# Mega_Shield-v4.net
KiCad netlist of a schematic drawn in EAGLE
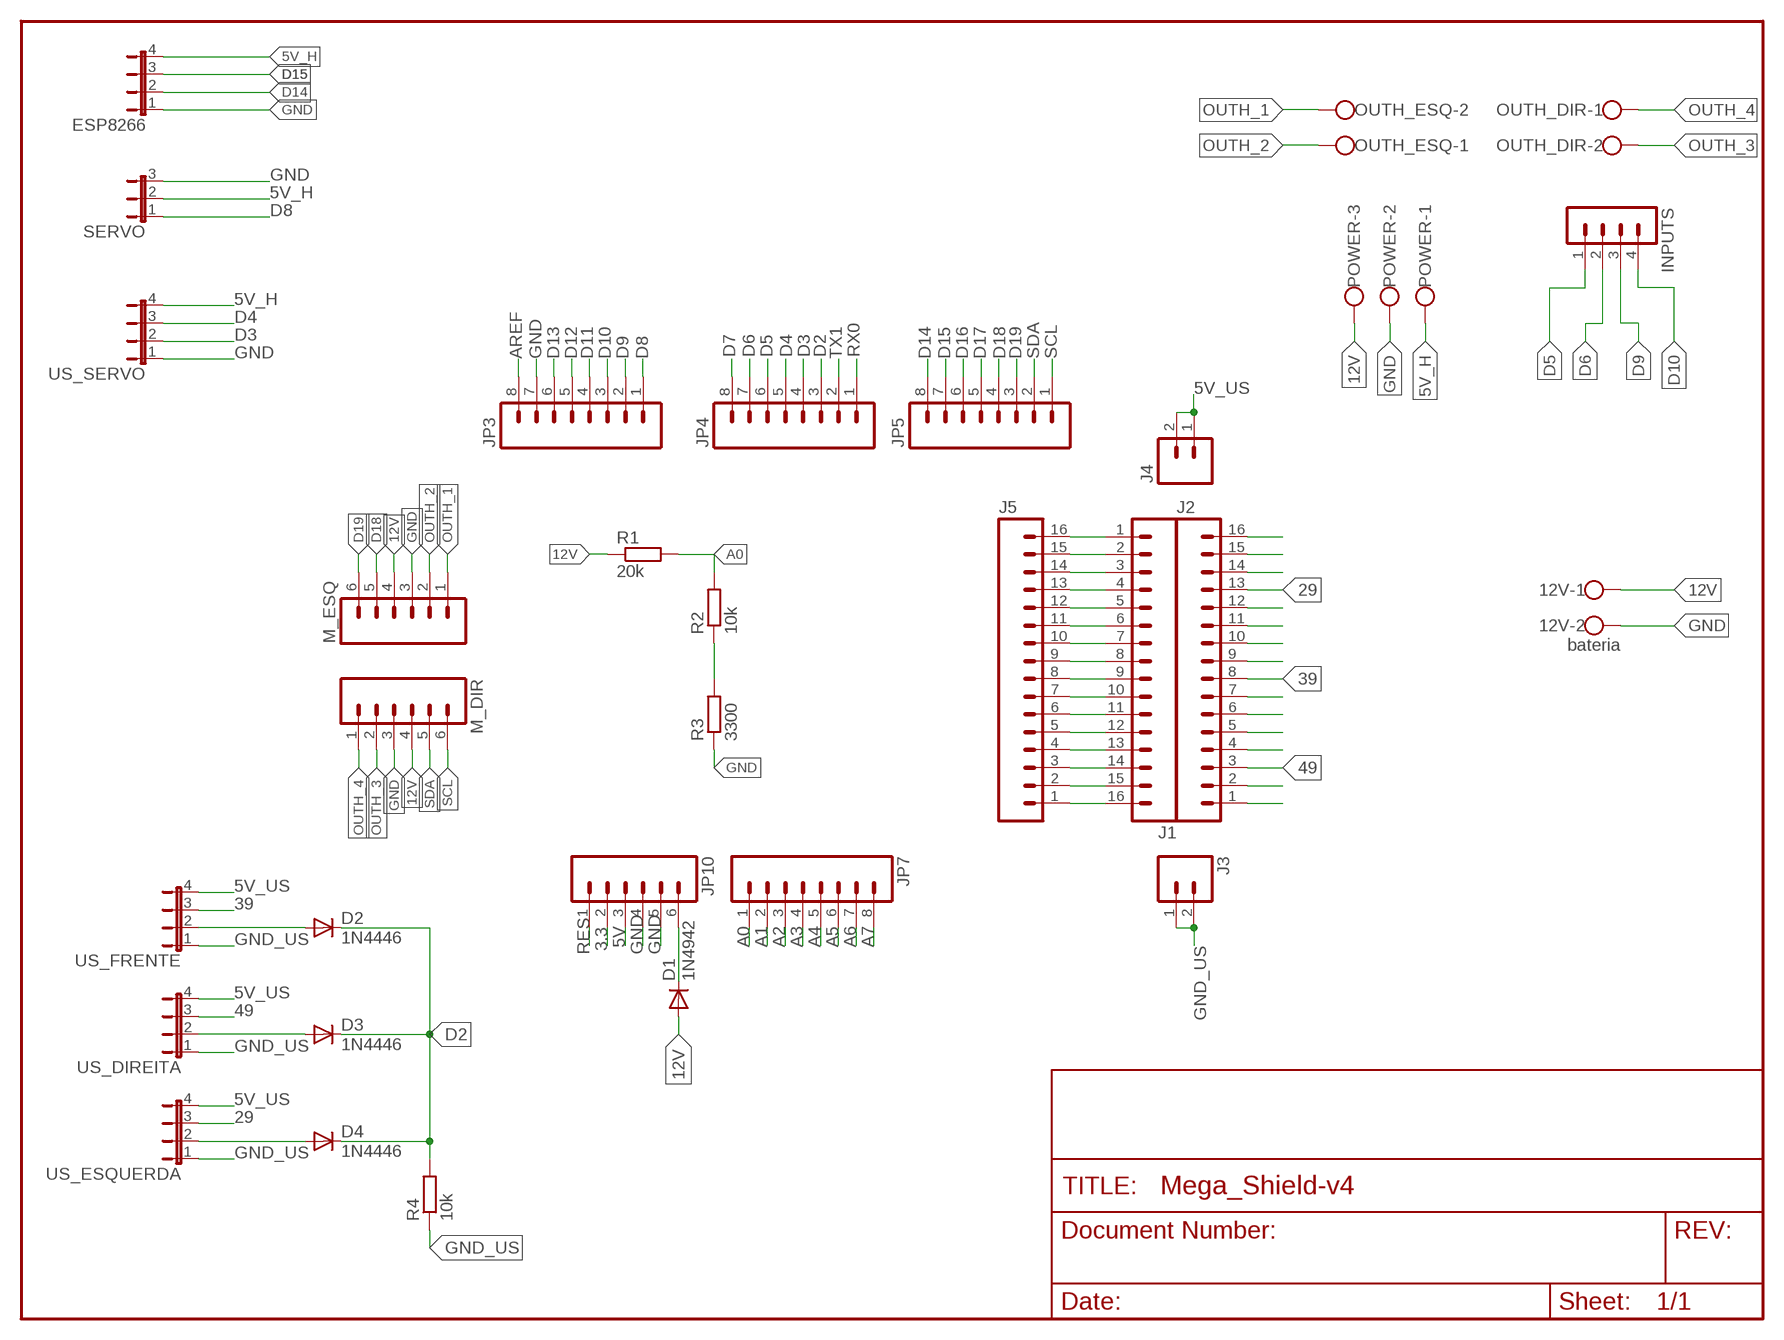
[diagram p0: schematic, sheet 1]

(export (version "E")
  (design (tool "Eeschema 10.0.6"))
  (components
    (comp (ref "12V")
      (value "bateria")
      (footprint "eagle-import:W237-102")
      (fields (field (name "MPN") "237-102"))
      (libsource (lib "eagle-import") (part "W237-102"))
    )
    (comp (ref "D1")
      (value "1N4942")
      (footprint "eagle-import:DO41-10")
      (libsource (lib "eagle-import") (part "1N4942"))
    )
    (comp (ref "D2")
      (value "1N4446")
      (footprint "eagle-import:DO35-10")
      (libsource (lib "eagle-import") (part "1N4446"))
    )
    (comp (ref "D3")
      (value "1N4446")
      (footprint "eagle-import:DO35-10")
      (libsource (lib "eagle-import") (part "1N4446"))
    )
    (comp (ref "D4")
      (value "1N4446")
      (footprint "eagle-import:DO35-10")
      (libsource (lib "eagle-import") (part "1N4446"))
    )
    (comp (ref "ESP8266")
      (value "JP4E")
      (footprint "eagle-import:JP4")
      (libsource (lib "eagle-import") (part "JP4E"))
    )
    (comp (ref "INPUTS")
      (value "MA04-1")
      (footprint "eagle-import:MA04-1")
      (libsource (lib "eagle-import") (part "MA04-1"))
    )
    (comp (ref "J1")
      (value "M16LOCK")
      (footprint "eagle-import:1X16_LOCK")
      (libsource (lib "eagle-import") (part "M16LOCK"))
    )
    (comp (ref "J2")
      (value "M16LOCK")
      (footprint "eagle-import:1X16_LOCK")
      (libsource (lib "eagle-import") (part "M16LOCK"))
    )
    (comp (ref "J3")
      (value "M02LOCK")
      (footprint "eagle-import:1X02_LOCK")
      (libsource (lib "eagle-import") (part "M02LOCK"))
    )
    (comp (ref "J4")
      (value "M02LOCK")
      (footprint "eagle-import:1X02_LOCK")
      (libsource (lib "eagle-import") (part "M02LOCK"))
    )
    (comp (ref "J5")
      (value "M16LOCK")
      (footprint "eagle-import:1X16_LOCK")
      (libsource (lib "eagle-import") (part "M16LOCK"))
    )
    (comp (ref "JP3")
      (value "M08LOCK")
      (footprint "eagle-import:1X08_LOCK")
      (libsource (lib "eagle-import") (part "M08LOCK"))
    )
    (comp (ref "JP4")
      (value "M08LOCK")
      (footprint "eagle-import:1X08_LOCK")
      (libsource (lib "eagle-import") (part "M08LOCK"))
    )
    (comp (ref "JP5")
      (value "M08LOCK")
      (footprint "eagle-import:1X08_LOCK")
      (libsource (lib "eagle-import") (part "M08LOCK"))
    )
    (comp (ref "JP7")
      (value "M08LOCK")
      (footprint "eagle-import:1X08_LOCK")
      (libsource (lib "eagle-import") (part "M08LOCK"))
    )
    (comp (ref "JP10")
      (value "M06LOCK")
      (footprint "eagle-import:1X06_LOCK")
      (libsource (lib "eagle-import") (part "M06LOCK"))
    )
    (comp (ref "M_DIR")
      (value "M06LOCK")
      (footprint "eagle-import:1X06_LOCK")
      (libsource (lib "eagle-import") (part "M06LOCK"))
    )
    (comp (ref "M_ESQ")
      (value "M06LOCK")
      (footprint "eagle-import:1X06_LOCK")
      (libsource (lib "eagle-import") (part "M06LOCK"))
    )
    (comp (ref "OUTH_DIR")
      (value "W237-102")
      (footprint "eagle-import:W237-102")
      (fields (field (name "MPN") "237-102"))
      (libsource (lib "eagle-import") (part "W237-102"))
    )
    (comp (ref "OUTH_ESQ")
      (value "W237-102")
      (footprint "eagle-import:W237-102")
      (fields (field (name "MPN") "237-102"))
      (libsource (lib "eagle-import") (part "W237-102"))
    )
    (comp (ref "POWER")
      (value "W237-103")
      (footprint "eagle-import:W237-103")
      (fields (field (name "MPN") "237-103"))
      (libsource (lib "eagle-import") (part "W237-103"))
    )
    (comp (ref "R1")
      (value "20k")
      (footprint "eagle-import:0207_10")
      (libsource (lib "eagle-import") (part "R-EU_0207/10"))
    )
    (comp (ref "R2")
      (value "10k")
      (footprint "eagle-import:0207_10")
      (libsource (lib "eagle-import") (part "R-EU_0207/10"))
    )
    (comp (ref "R3")
      (value "3300")
      (footprint "eagle-import:0207_10")
      (libsource (lib "eagle-import") (part "R-EU_0207/10"))
    )
    (comp (ref "R4")
      (value "10k")
      (footprint "eagle-import:0207_10")
      (libsource (lib "eagle-import") (part "R-EU_0207/10"))
    )
    (comp (ref "SERVO")
      (value "JP2W")
      (footprint "eagle-import:JP2W")
      (libsource (lib "eagle-import") (part "JP2W"))
    )
    (comp (ref "US_DIREITA")
      (value "JP4E")
      (footprint "eagle-import:JP4")
      (libsource (lib "eagle-import") (part "JP4E"))
    )
    (comp (ref "US_ESQUERDA")
      (value "JP4E")
      (footprint "eagle-import:JP4")
      (libsource (lib "eagle-import") (part "JP4E"))
    )
    (comp (ref "US_FRENTE")
      (value "JP4E")
      (footprint "eagle-import:JP4")
      (libsource (lib "eagle-import") (part "JP4E"))
    )
    (comp (ref "US_SERVO")
      (value "JP4E")
      (footprint "eagle-import:JP4")
      (libsource (lib "eagle-import") (part "JP4E"))
    )
  )
  (nets
    (net (code "1") (name "/3.3") (class "Default")
      (node (ref "JP10") (pin "2") (pinfunction "2_2") (pintype "passive"))
    )
    (net (code "2") (name "/5V") (class "Default")
      (node (ref "JP10") (pin "3") (pinfunction "3_3") (pintype "passive"))
    )
    (net (code "3") (name "/5V_US") (class "Default")
      (node (ref "J4") (pin "1") (pinfunction "1_1") (pintype "passive"))
      (node (ref "J4") (pin "2") (pinfunction "2_2") (pintype "passive"))
      (node (ref "US_DIREITA") (pin "4") (pinfunction "4_4") (pintype "passive"))
      (node (ref "US_ESQUERDA") (pin "4") (pinfunction "4_4") (pintype "passive"))
      (node (ref "US_FRENTE") (pin "4") (pinfunction "4_4") (pintype "passive"))
    )
    (net (code "4") (name "/A1") (class "Default")
      (node (ref "JP7") (pin "2") (pinfunction "2_2") (pintype "passive"))
    )
    (net (code "5") (name "/A2") (class "Default")
      (node (ref "JP7") (pin "3") (pinfunction "3_3") (pintype "passive"))
    )
    (net (code "6") (name "/A3") (class "Default")
      (node (ref "JP7") (pin "4") (pinfunction "4_4") (pintype "passive"))
    )
    (net (code "7") (name "/A4") (class "Default")
      (node (ref "JP7") (pin "5") (pinfunction "5_5") (pintype "passive"))
    )
    (net (code "8") (name "/A5") (class "Default")
      (node (ref "JP7") (pin "6") (pinfunction "6_6") (pintype "passive"))
    )
    (net (code "9") (name "/A6") (class "Default")
      (node (ref "JP7") (pin "7") (pinfunction "7_7") (pintype "passive"))
    )
    (net (code "10") (name "/A7") (class "Default")
      (node (ref "JP7") (pin "8") (pinfunction "8_8") (pintype "passive"))
    )
    (net (code "11") (name "/AREF") (class "Default")
      (node (ref "JP3") (pin "8") (pinfunction "8_8") (pintype "passive"))
    )
    (net (code "12") (name "/D3") (class "Default")
      (node (ref "JP4") (pin "4") (pinfunction "4_4") (pintype "passive"))
      (node (ref "US_SERVO") (pin "2") (pinfunction "2_2") (pintype "passive"))
    )
    (net (code "13") (name "/D4") (class "Default")
      (node (ref "JP4") (pin "5") (pinfunction "5_5") (pintype "passive"))
      (node (ref "US_SERVO") (pin "3") (pinfunction "3_3") (pintype "passive"))
    )
    (net (code "14") (name "/D7") (class "Default")
      (node (ref "JP4") (pin "8") (pinfunction "8_8") (pintype "passive"))
    )
    (net (code "15") (name "/D8") (class "Default")
      (node (ref "JP3") (pin "1") (pinfunction "1_1") (pintype "passive"))
      (node (ref "SERVO") (pin "1") (pinfunction "1_1") (pintype "passive"))
    )
    (net (code "16") (name "/D11") (class "Default")
      (node (ref "JP3") (pin "4") (pinfunction "4_4") (pintype "passive"))
    )
    (net (code "17") (name "/D12") (class "Default")
      (node (ref "JP3") (pin "5") (pinfunction "5_5") (pintype "passive"))
    )
    (net (code "18") (name "/D13") (class "Default")
      (node (ref "JP3") (pin "6") (pinfunction "6_6") (pintype "passive"))
    )
    (net (code "19") (name "/D16") (class "Default")
      (node (ref "JP5") (pin "6") (pinfunction "6_6") (pintype "passive"))
    )
    (net (code "20") (name "/D17") (class "Default")
      (node (ref "JP5") (pin "5") (pinfunction "5_5") (pintype "passive"))
    )
    (net (code "21") (name "/RES") (class "Default")
      (node (ref "JP10") (pin "1") (pinfunction "1_1") (pintype "passive"))
    )
    (net (code "22") (name "/RX0") (class "Default")
      (node (ref "JP4") (pin "1") (pinfunction "1_1") (pintype "passive"))
    )
    (net (code "23") (name "/TX1") (class "Default")
      (node (ref "JP4") (pin "2") (pinfunction "2_2") (pintype "passive"))
    )
    (net (code "24") (name "5V_H") (class "Default")
      (node (ref "ESP8266") (pin "4") (pinfunction "4_4") (pintype "passive"))
      (node (ref "POWER") (pin "1") (pinfunction "KL_1") (pintype "passive"))
      (node (ref "SERVO") (pin "2") (pinfunction "2_2") (pintype "passive"))
      (node (ref "US_SERVO") (pin "4") (pinfunction "4_4") (pintype "passive"))
    )
    (net (code "25") (name "12V") (class "Default")
      (node (ref "12V") (pin "1") (pinfunction "KL_1") (pintype "passive"))
      (node (ref "D1") (pin "A") (pinfunction "A_A") (pintype "passive"))
      (node (ref "M_DIR") (pin "4") (pinfunction "4_4") (pintype "passive"))
      (node (ref "M_ESQ") (pin "4") (pinfunction "4_4") (pintype "passive"))
      (node (ref "POWER") (pin "3") (pinfunction "KL_3") (pintype "passive"))
      (node (ref "R1") (pin "1") (pinfunction "1_1") (pintype "passive"))
    )
    (net (code "26") (name "29") (class "Default")
      (node (ref "J2") (pin "13") (pinfunction "13_13") (pintype "passive"))
      (node (ref "US_ESQUERDA") (pin "3") (pinfunction "3_3") (pintype "passive"))
    )
    (net (code "27") (name "39") (class "Default")
      (node (ref "J2") (pin "8") (pinfunction "8_8") (pintype "passive"))
      (node (ref "US_FRENTE") (pin "3") (pinfunction "3_3") (pintype "passive"))
    )
    (net (code "28") (name "49") (class "Default")
      (node (ref "J2") (pin "3") (pinfunction "3_3") (pintype "passive"))
      (node (ref "US_DIREITA") (pin "3") (pinfunction "3_3") (pintype "passive"))
    )
    (net (code "29") (name "A0") (class "Default")
      (node (ref "JP7") (pin "1") (pinfunction "1_1") (pintype "passive"))
      (node (ref "R1") (pin "2") (pinfunction "2_2") (pintype "passive"))
      (node (ref "R2") (pin "2") (pinfunction "2_2") (pintype "passive"))
    )
    (net (code "30") (name "D2") (class "Default")
      (node (ref "D2") (pin "C") (pinfunction "C_C") (pintype "passive"))
      (node (ref "D3") (pin "C") (pinfunction "C_C") (pintype "passive"))
      (node (ref "D4") (pin "C") (pinfunction "C_C") (pintype "passive"))
      (node (ref "JP4") (pin "3") (pinfunction "3_3") (pintype "passive"))
      (node (ref "R4") (pin "2") (pinfunction "2_2") (pintype "passive"))
    )
    (net (code "31") (name "D5") (class "Default")
      (node (ref "INPUTS") (pin "1") (pinfunction "1_1") (pintype "passive"))
      (node (ref "JP4") (pin "6") (pinfunction "6_6") (pintype "passive"))
    )
    (net (code "32") (name "D6") (class "Default")
      (node (ref "INPUTS") (pin "2") (pinfunction "2_2") (pintype "passive"))
      (node (ref "JP4") (pin "7") (pinfunction "7_7") (pintype "passive"))
    )
    (net (code "33") (name "D9") (class "Default")
      (node (ref "INPUTS") (pin "3") (pinfunction "3_3") (pintype "passive"))
      (node (ref "JP3") (pin "2") (pinfunction "2_2") (pintype "passive"))
    )
    (net (code "34") (name "D10") (class "Default")
      (node (ref "INPUTS") (pin "4") (pinfunction "4_4") (pintype "passive"))
      (node (ref "JP3") (pin "3") (pinfunction "3_3") (pintype "passive"))
    )
    (net (code "35") (name "D14") (class "Default")
      (node (ref "ESP8266") (pin "2") (pinfunction "2_2") (pintype "passive"))
      (node (ref "JP5") (pin "8") (pinfunction "8_8") (pintype "passive"))
    )
    (net (code "36") (name "D15") (class "Default")
      (node (ref "ESP8266") (pin "3") (pinfunction "3_3") (pintype "passive"))
      (node (ref "JP5") (pin "7") (pinfunction "7_7") (pintype "passive"))
    )
    (net (code "37") (name "D18") (class "Default")
      (node (ref "JP5") (pin "4") (pinfunction "4_4") (pintype "passive"))
      (node (ref "M_ESQ") (pin "5") (pinfunction "5_5") (pintype "passive"))
    )
    (net (code "38") (name "D19") (class "Default")
      (node (ref "JP5") (pin "3") (pinfunction "3_3") (pintype "passive"))
      (node (ref "M_ESQ") (pin "6") (pinfunction "6_6") (pintype "passive"))
    )
    (net (code "39") (name "GND") (class "Default")
      (node (ref "12V") (pin "2") (pinfunction "KL_2") (pintype "passive"))
      (node (ref "ESP8266") (pin "1") (pinfunction "1_1") (pintype "passive"))
      (node (ref "JP10") (pin "4") (pinfunction "4_4") (pintype "passive"))
      (node (ref "JP10") (pin "5") (pinfunction "5_5") (pintype "passive"))
      (node (ref "JP3") (pin "7") (pinfunction "7_7") (pintype "passive"))
      (node (ref "M_DIR") (pin "3") (pinfunction "3_3") (pintype "passive"))
      (node (ref "M_ESQ") (pin "3") (pinfunction "3_3") (pintype "passive"))
      (node (ref "POWER") (pin "2") (pinfunction "KL_2") (pintype "passive"))
      (node (ref "R3") (pin "1") (pinfunction "1_1") (pintype "passive"))
      (node (ref "SERVO") (pin "3") (pinfunction "3_3") (pintype "passive"))
      (node (ref "US_SERVO") (pin "1") (pinfunction "1_1") (pintype "passive"))
    )
    (net (code "40") (name "GND_US") (class "Default")
      (node (ref "J3") (pin "1") (pinfunction "1_1") (pintype "passive"))
      (node (ref "J3") (pin "2") (pinfunction "2_2") (pintype "passive"))
      (node (ref "R4") (pin "1") (pinfunction "1_1") (pintype "passive"))
      (node (ref "US_DIREITA") (pin "1") (pinfunction "1_1") (pintype "passive"))
      (node (ref "US_ESQUERDA") (pin "1") (pinfunction "1_1") (pintype "passive"))
      (node (ref "US_FRENTE") (pin "1") (pinfunction "1_1") (pintype "passive"))
    )
    (net (code "41") (name "Net-(D1-PadC)") (class "Default")
      (node (ref "D1") (pin "C") (pinfunction "C_C") (pintype "passive"))
      (node (ref "JP10") (pin "6") (pinfunction "6_6") (pintype "passive"))
    )
    (net (code "42") (name "Net-(D2-PadA)") (class "Default")
      (node (ref "D2") (pin "A") (pinfunction "A_A") (pintype "passive"))
      (node (ref "US_FRENTE") (pin "2") (pinfunction "2_2") (pintype "passive"))
    )
    (net (code "43") (name "Net-(D3-PadA)") (class "Default")
      (node (ref "D3") (pin "A") (pinfunction "A_A") (pintype "passive"))
      (node (ref "US_DIREITA") (pin "2") (pinfunction "2_2") (pintype "passive"))
    )
    (net (code "44") (name "Net-(D4-PadA)") (class "Default")
      (node (ref "D4") (pin "A") (pinfunction "A_A") (pintype "passive"))
      (node (ref "US_ESQUERDA") (pin "2") (pinfunction "2_2") (pintype "passive"))
    )
    (net (code "45") (name "Net-(J1-Pad1)") (class "Default")
      (node (ref "J1") (pin "1") (pinfunction "1_1") (pintype "passive"))
      (node (ref "J5") (pin "16") (pinfunction "16_16") (pintype "passive"))
    )
    (net (code "46") (name "Net-(J1-Pad2)") (class "Default")
      (node (ref "J1") (pin "2") (pinfunction "2_2") (pintype "passive"))
      (node (ref "J5") (pin "15") (pinfunction "15_15") (pintype "passive"))
    )
    (net (code "47") (name "Net-(J1-Pad3)") (class "Default")
      (node (ref "J1") (pin "3") (pinfunction "3_3") (pintype "passive"))
      (node (ref "J5") (pin "14") (pinfunction "14_14") (pintype "passive"))
    )
    (net (code "48") (name "Net-(J1-Pad4)") (class "Default")
      (node (ref "J1") (pin "4") (pinfunction "4_4") (pintype "passive"))
      (node (ref "J5") (pin "13") (pinfunction "13_13") (pintype "passive"))
    )
    (net (code "49") (name "Net-(J1-Pad5)") (class "Default")
      (node (ref "J1") (pin "5") (pinfunction "5_5") (pintype "passive"))
      (node (ref "J5") (pin "12") (pinfunction "12_12") (pintype "passive"))
    )
    (net (code "50") (name "Net-(J1-Pad6)") (class "Default")
      (node (ref "J1") (pin "6") (pinfunction "6_6") (pintype "passive"))
      (node (ref "J5") (pin "11") (pinfunction "11_11") (pintype "passive"))
    )
    (net (code "51") (name "Net-(J1-Pad7)") (class "Default")
      (node (ref "J1") (pin "7") (pinfunction "7_7") (pintype "passive"))
      (node (ref "J5") (pin "10") (pinfunction "10_10") (pintype "passive"))
    )
    (net (code "52") (name "Net-(J1-Pad8)") (class "Default")
      (node (ref "J1") (pin "8") (pinfunction "8_8") (pintype "passive"))
      (node (ref "J5") (pin "9") (pinfunction "9_9") (pintype "passive"))
    )
    (net (code "53") (name "Net-(J1-Pad9)") (class "Default")
      (node (ref "J1") (pin "9") (pinfunction "9_9") (pintype "passive"))
      (node (ref "J5") (pin "8") (pinfunction "8_8") (pintype "passive"))
    )
    (net (code "54") (name "Net-(J1-Pad10)") (class "Default")
      (node (ref "J1") (pin "10") (pinfunction "10_10") (pintype "passive"))
      (node (ref "J5") (pin "7") (pinfunction "7_7") (pintype "passive"))
    )
    (net (code "55") (name "Net-(J1-Pad11)") (class "Default")
      (node (ref "J1") (pin "11") (pinfunction "11_11") (pintype "passive"))
      (node (ref "J5") (pin "6") (pinfunction "6_6") (pintype "passive"))
    )
    (net (code "56") (name "Net-(J1-Pad12)") (class "Default")
      (node (ref "J1") (pin "12") (pinfunction "12_12") (pintype "passive"))
      (node (ref "J5") (pin "5") (pinfunction "5_5") (pintype "passive"))
    )
    (net (code "57") (name "Net-(J1-Pad13)") (class "Default")
      (node (ref "J1") (pin "13") (pinfunction "13_13") (pintype "passive"))
      (node (ref "J5") (pin "4") (pinfunction "4_4") (pintype "passive"))
    )
    (net (code "58") (name "Net-(J1-Pad14)") (class "Default")
      (node (ref "J1") (pin "14") (pinfunction "14_14") (pintype "passive"))
      (node (ref "J5") (pin "3") (pinfunction "3_3") (pintype "passive"))
    )
    (net (code "59") (name "Net-(J1-Pad15)") (class "Default")
      (node (ref "J1") (pin "15") (pinfunction "15_15") (pintype "passive"))
      (node (ref "J5") (pin "2") (pinfunction "2_2") (pintype "passive"))
    )
    (net (code "60") (name "Net-(J1-Pad16)") (class "Default")
      (node (ref "J1") (pin "16") (pinfunction "16_16") (pintype "passive"))
      (node (ref "J5") (pin "1") (pinfunction "1_1") (pintype "passive"))
    )
    (net (code "61") (name "Net-(R2-Pad1)") (class "Default")
      (node (ref "R2") (pin "1") (pinfunction "1_1") (pintype "passive"))
      (node (ref "R3") (pin "2") (pinfunction "2_2") (pintype "passive"))
    )
    (net (code "62") (name "OUTH_1") (class "Default")
      (node (ref "M_ESQ") (pin "1") (pinfunction "1_1") (pintype "passive"))
      (node (ref "OUTH_ESQ") (pin "2") (pinfunction "KL_2") (pintype "passive"))
    )
    (net (code "63") (name "OUTH_2") (class "Default")
      (node (ref "M_ESQ") (pin "2") (pinfunction "2_2") (pintype "passive"))
      (node (ref "OUTH_ESQ") (pin "1") (pinfunction "KL_1") (pintype "passive"))
    )
    (net (code "64") (name "OUTH_3") (class "Default")
      (node (ref "M_DIR") (pin "2") (pinfunction "2_2") (pintype "passive"))
      (node (ref "OUTH_DIR") (pin "2") (pinfunction "KL_2") (pintype "passive"))
    )
    (net (code "65") (name "OUTH_4") (class "Default")
      (node (ref "M_DIR") (pin "1") (pinfunction "1_1") (pintype "passive"))
      (node (ref "OUTH_DIR") (pin "1") (pinfunction "KL_1") (pintype "passive"))
    )
    (net (code "66") (name "SCL") (class "Default")
      (node (ref "JP5") (pin "1") (pinfunction "1_1") (pintype "passive"))
      (node (ref "M_DIR") (pin "6") (pinfunction "6_6") (pintype "passive"))
    )
    (net (code "67") (name "SDA") (class "Default")
      (node (ref "JP5") (pin "2") (pinfunction "2_2") (pintype "passive"))
      (node (ref "M_DIR") (pin "5") (pinfunction "5_5") (pintype "passive"))
    )
    (net (code "68") (name "unconnected-(J2-Pad1)") (class "Default")
      (node (ref "J2") (pin "1") (pinfunction "1_1") (pintype "passive"))
    )
    (net (code "69") (name "unconnected-(J2-Pad2)") (class "Default")
      (node (ref "J2") (pin "2") (pinfunction "2_2") (pintype "passive"))
    )
    (net (code "70") (name "unconnected-(J2-Pad4)") (class "Default")
      (node (ref "J2") (pin "4") (pinfunction "4_4") (pintype "passive"))
    )
    (net (code "71") (name "unconnected-(J2-Pad5)") (class "Default")
      (node (ref "J2") (pin "5") (pinfunction "5_5") (pintype "passive"))
    )
    (net (code "72") (name "unconnected-(J2-Pad6)") (class "Default")
      (node (ref "J2") (pin "6") (pinfunction "6_6") (pintype "passive"))
    )
    (net (code "73") (name "unconnected-(J2-Pad7)") (class "Default")
      (node (ref "J2") (pin "7") (pinfunction "7_7") (pintype "passive"))
    )
    (net (code "74") (name "unconnected-(J2-Pad9)") (class "Default")
      (node (ref "J2") (pin "9") (pinfunction "9_9") (pintype "passive"))
    )
    (net (code "75") (name "unconnected-(J2-Pad10)") (class "Default")
      (node (ref "J2") (pin "10") (pinfunction "10_10") (pintype "passive"))
    )
    (net (code "76") (name "unconnected-(J2-Pad11)") (class "Default")
      (node (ref "J2") (pin "11") (pinfunction "11_11") (pintype "passive"))
    )
    (net (code "77") (name "unconnected-(J2-Pad12)") (class "Default")
      (node (ref "J2") (pin "12") (pinfunction "12_12") (pintype "passive"))
    )
    (net (code "78") (name "unconnected-(J2-Pad14)") (class "Default")
      (node (ref "J2") (pin "14") (pinfunction "14_14") (pintype "passive"))
    )
    (net (code "79") (name "unconnected-(J2-Pad15)") (class "Default")
      (node (ref "J2") (pin "15") (pinfunction "15_15") (pintype "passive"))
    )
    (net (code "80") (name "unconnected-(J2-Pad16)") (class "Default")
      (node (ref "J2") (pin "16") (pinfunction "16_16") (pintype "passive"))
    )
  )
)
